# 21_USB.net
KiCad netlist of a schematic drawn in Altium Designer
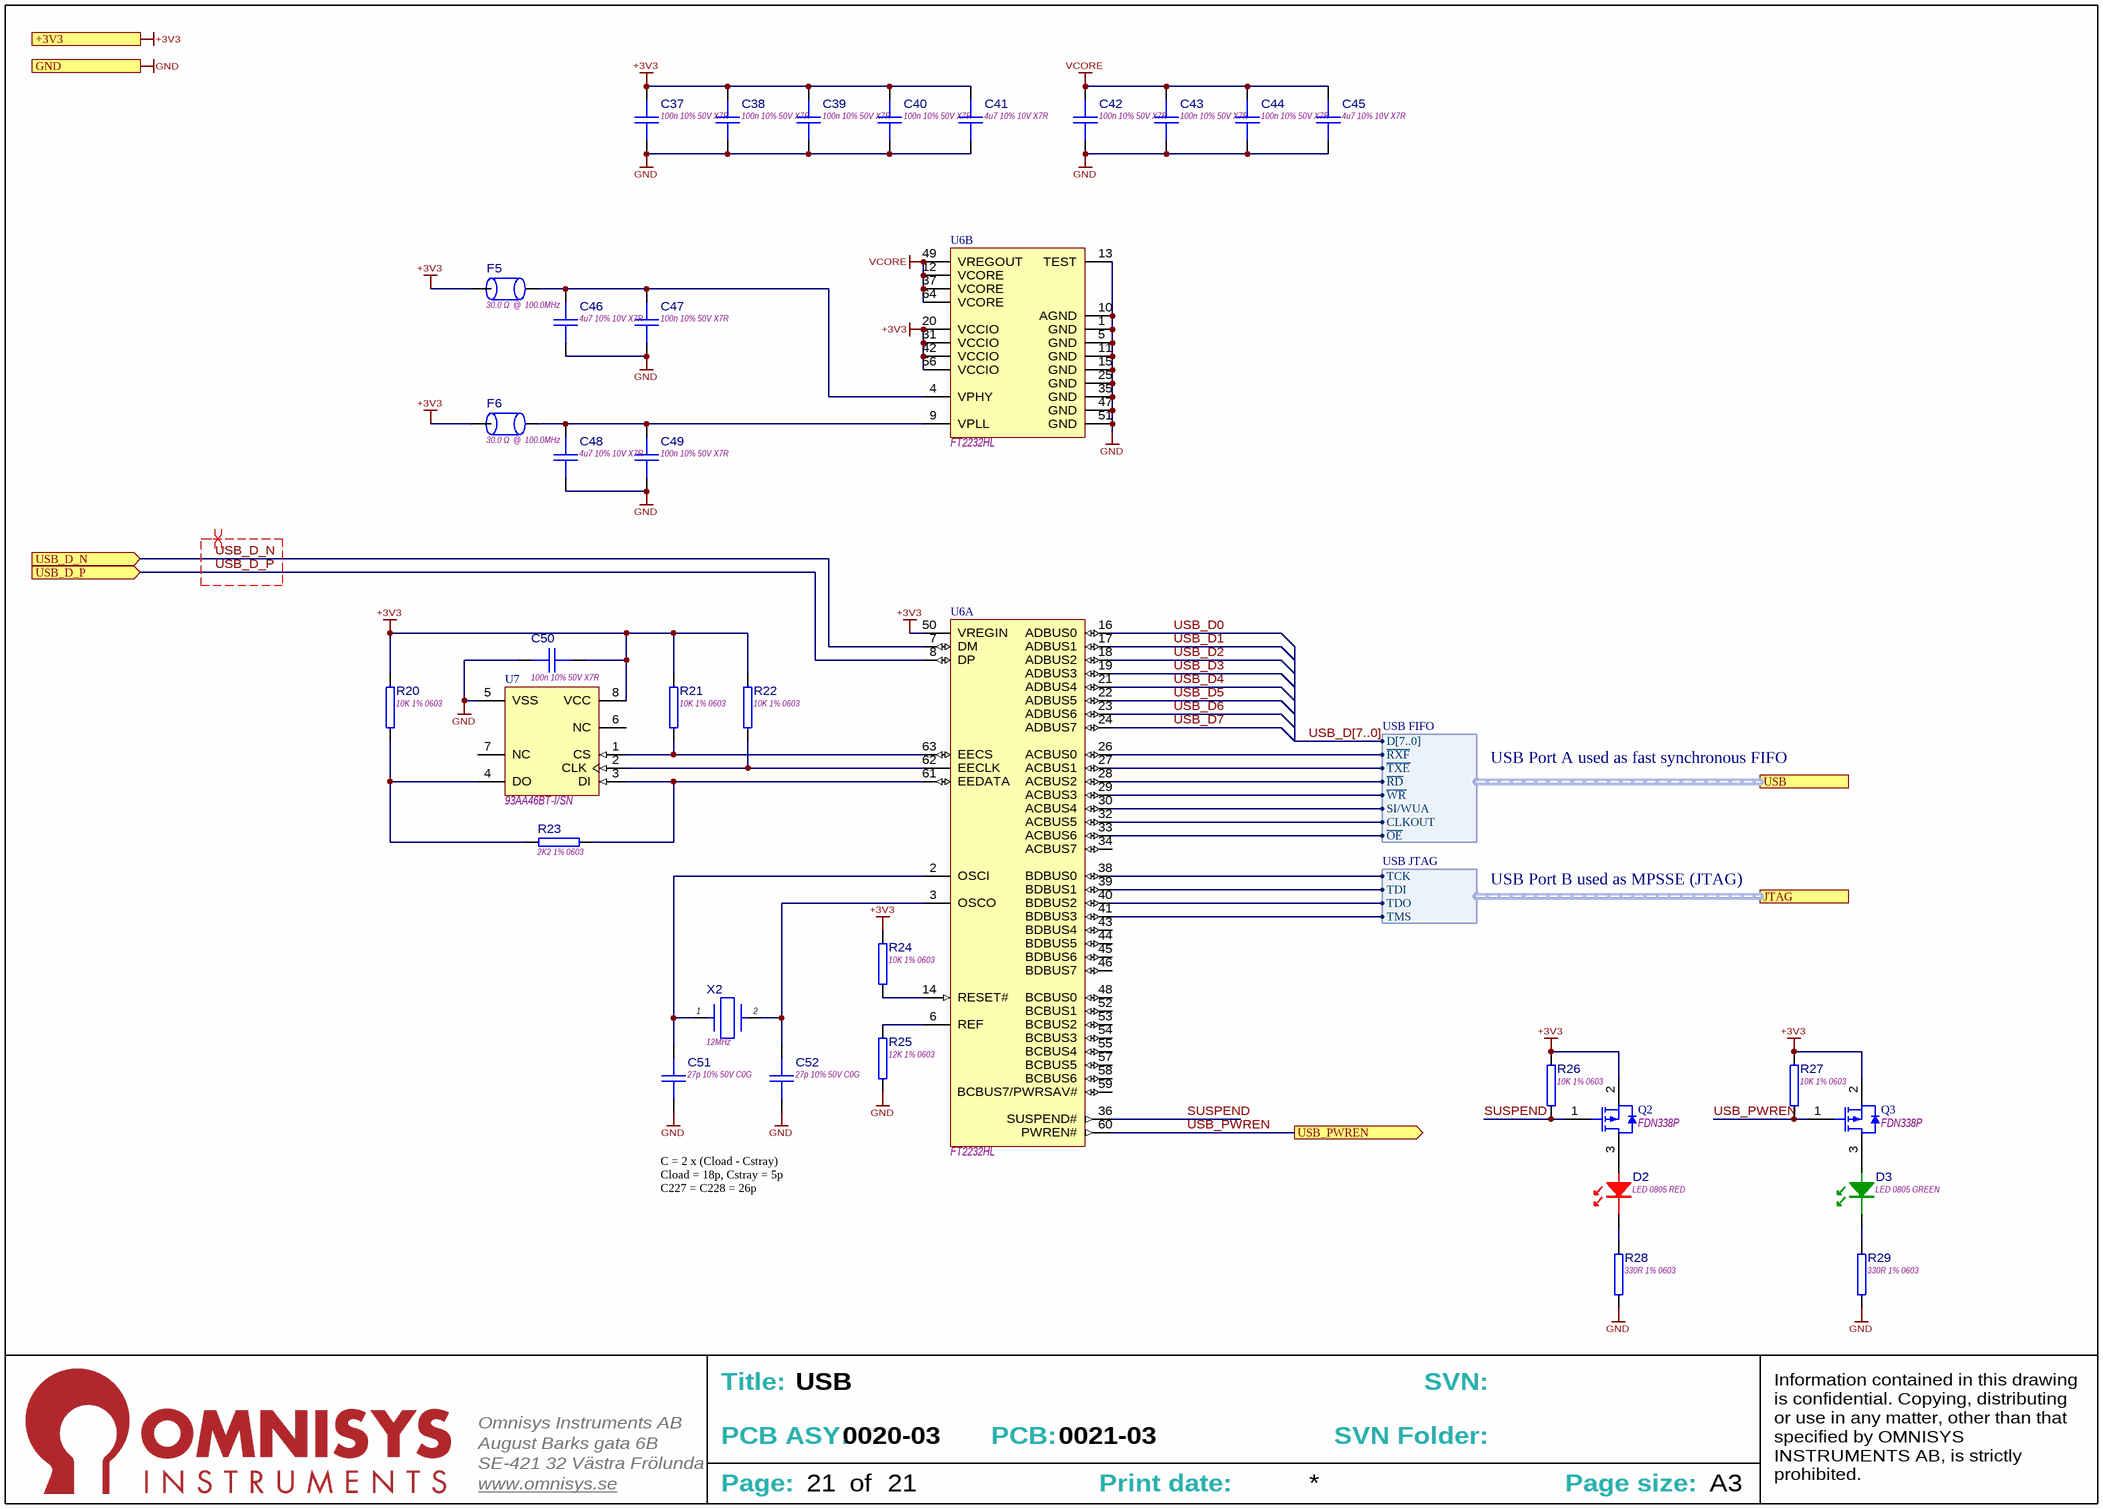
[diagram p0: [21] USB.SchDoc]

(export (version "E")
  (design (tool "Eeschema 10.0.6"))
  (components
    (comp (ref "C37")
      (value "100n 10% 50V X7R")
      (footprint "CAPC1608X90N")
      (description "Ceramic Chip Capacitor, 0603/1608")
      (fields (field (name "TOLERANCE") "10%"))
      (libsource (lib "Omnisys Vault") (part "CAP-2PIN"))
    )
    (comp (ref "C38")
      (value "100n 10% 50V X7R")
      (footprint "CAPC1608X90N")
      (description "Ceramic Chip Capacitor, 0603/1608")
      (fields (field (name "TOLERANCE") "10%"))
      (libsource (lib "Omnisys Vault") (part "CAP-2PIN"))
    )
    (comp (ref "C39")
      (value "100n 10% 50V X7R")
      (footprint "CAPC1608X90N")
      (description "Ceramic Chip Capacitor, 0603/1608")
      (fields (field (name "TOLERANCE") "10%"))
      (libsource (lib "Omnisys Vault") (part "CAP-2PIN"))
    )
    (comp (ref "C40")
      (value "100n 10% 50V X7R")
      (footprint "CAPC1608X90N")
      (description "Ceramic Chip Capacitor, 0603/1608")
      (fields (field (name "TOLERANCE") "10%"))
      (libsource (lib "Omnisys Vault") (part "CAP-2PIN"))
    )
    (comp (ref "C41")
      (value "4u7 10% 10V X7R")
      (footprint "CAPC2012X145N")
      (description "Ceramic Chip Capacitor, 0805/2012")
      (fields (field (name "TOLERANCE") "10%"))
      (libsource (lib "Omnisys Vault") (part "CAP-2PIN"))
    )
    (comp (ref "C42")
      (value "100n 10% 50V X7R")
      (footprint "CAPC1608X90N")
      (description "Ceramic Chip Capacitor, 0603/1608")
      (fields (field (name "TOLERANCE") "10%"))
      (libsource (lib "Omnisys Vault") (part "CAP-2PIN"))
    )
    (comp (ref "C43")
      (value "100n 10% 50V X7R")
      (footprint "CAPC1608X90N")
      (description "Ceramic Chip Capacitor, 0603/1608")
      (fields (field (name "TOLERANCE") "10%"))
      (libsource (lib "Omnisys Vault") (part "CAP-2PIN"))
    )
    (comp (ref "C44")
      (value "100n 10% 50V X7R")
      (footprint "CAPC1608X90N")
      (description "Ceramic Chip Capacitor, 0603/1608")
      (fields (field (name "TOLERANCE") "10%"))
      (libsource (lib "Omnisys Vault") (part "CAP-2PIN"))
    )
    (comp (ref "C45")
      (value "4u7 10% 10V X7R")
      (footprint "CAPC2012X145N")
      (description "Ceramic Chip Capacitor, 0805/2012")
      (fields (field (name "TOLERANCE") "10%"))
      (libsource (lib "Omnisys Vault") (part "CAP-2PIN"))
    )
    (comp (ref "C46")
      (value "4u7 10% 10V X7R")
      (footprint "CAPC2012X145N")
      (description "Ceramic Chip Capacitor, 0805/2012")
      (fields (field (name "TOLERANCE") "10%"))
      (libsource (lib "Omnisys Vault") (part "CAP-2PIN"))
    )
    (comp (ref "C47")
      (value "100n 10% 50V X7R")
      (footprint "CAPC1608X90N")
      (description "Ceramic Chip Capacitor, 0603/1608")
      (fields (field (name "TOLERANCE") "10%"))
      (libsource (lib "Omnisys Vault") (part "CAP-2PIN"))
    )
    (comp (ref "C48")
      (value "4u7 10% 10V X7R")
      (footprint "CAPC2012X145N")
      (description "Ceramic Chip Capacitor, 0805/2012")
      (fields (field (name "TOLERANCE") "10%"))
      (libsource (lib "Omnisys Vault") (part "CAP-2PIN"))
    )
    (comp (ref "C49")
      (value "100n 10% 50V X7R")
      (footprint "CAPC1608X90N")
      (description "Ceramic Chip Capacitor, 0603/1608")
      (fields (field (name "TOLERANCE") "10%"))
      (libsource (lib "Omnisys Vault") (part "CAP-2PIN"))
    )
    (comp (ref "C50")
      (value "100n 10% 50V X7R")
      (footprint "CAPC1608X90N")
      (description "Ceramic Chip Capacitor, 0603/1608")
      (fields (field (name "TOLERANCE") "10%"))
      (libsource (lib "Omnisys Vault") (part "CAP-2PIN"))
    )
    (comp (ref "C51")
      (value "27p 10% 50V C0G")
      (footprint "CAPC1608X90N")
      (description "Ceramic Chip Capacitor, 0603/1608")
      (fields (field (name "TOLERANCE") "5%"))
      (libsource (lib "Omnisys Vault") (part "CAP-2PIN"))
    )
    (comp (ref "C52")
      (value "27p 10% 50V C0G")
      (footprint "CAPC1608X90N")
      (description "Ceramic Chip Capacitor, 0603/1608")
      (fields (field (name "TOLERANCE") "5%"))
      (libsource (lib "Omnisys Vault") (part "CAP-2PIN"))
    )
    (comp (ref "D2")
      (value "LED 0805 RED")
      (footprint "LED2012-RED")
      (libsource (lib "Omnisys Vault") (part "LED-2PIN-RED"))
    )
    (comp (ref "D3")
      (value "LED 0805 GREEN")
      (footprint "LED2012-GREEN")
      (libsource (lib "Omnisys Vault") (part "LED-2PIN-GREEN"))
    )
    (comp (ref "F5")
      (value "30.0 Ω  @  100.0MHz")
      (footprint "INDC2012X11N")
      (description "Ferrite bead, Würth Elektronik WE-CBF 2012 (0805), 74279206 ,  30.0 Ω  @  100.0MHz")
      (fields (field (name "PARTNUMBER") "74279206"))
      (libsource (lib "Omnisys Vault") (part "BEAD-2PIN"))
    )
    (comp (ref "F6")
      (value "30.0 Ω  @  100.0MHz")
      (footprint "INDC2012X11N")
      (description "Ferrite bead, Würth Elektronik WE-CBF 2012 (0805), 74279206 ,  30.0 Ω  @  100.0MHz")
      (fields (field (name "PARTNUMBER") "74279206"))
      (libsource (lib "Omnisys Vault") (part "BEAD-2PIN"))
    )
    (comp (ref "Q2")
      (value "FDN338P")
      (footprint "SOT95P230X110-3N")
      (description "ON SEMICONDUCTOR - FDN338P - P CHANNEL MOSFET, -20V, 1.6A SUPER SOT-3")
      (libsource (lib "Omnisys Vault") (part "PEMOS-GSD-3"))
    )
    (comp (ref "Q3")
      (value "FDN338P")
      (footprint "SOT95P230X110-3N")
      (description "ON SEMICONDUCTOR - FDN338P - P CHANNEL MOSFET, -20V, 1.6A SUPER SOT-3")
      (libsource (lib "Omnisys Vault") (part "PEMOS-GSD-3"))
    )
    (comp (ref "R20")
      (value "10K 1% 0603")
      (footprint "RESC1608N")
      (description "Thick film Chip Resistor, 0603/1608")
      (fields (field (name "POWER") "100mW") (field (name "TOLERANCE") "1%"))
      (libsource (lib "Omnisys Vault") (part "RES-2PIN"))
    )
    (comp (ref "R21")
      (value "10K 1% 0603")
      (footprint "RESC1608N")
      (description "Thick film Chip Resistor, 0603/1608")
      (fields (field (name "POWER") "100mW") (field (name "TOLERANCE") "1%"))
      (libsource (lib "Omnisys Vault") (part "RES-2PIN"))
    )
    (comp (ref "R22")
      (value "10K 1% 0603")
      (footprint "RESC1608N")
      (description "Thick film Chip Resistor, 0603/1608")
      (fields (field (name "POWER") "100mW") (field (name "TOLERANCE") "1%"))
      (libsource (lib "Omnisys Vault") (part "RES-2PIN"))
    )
    (comp (ref "R23")
      (value "2K2 1% 0603")
      (footprint "RESC1608N")
      (description "Thick film Chip Resistor, 0603/1608")
      (fields (field (name "POWER") "100mW") (field (name "TOLERANCE") "1%"))
      (libsource (lib "Omnisys Vault") (part "RES-2PIN"))
    )
    (comp (ref "R24")
      (value "10K 1% 0603")
      (footprint "RESC1608N")
      (description "Thick film Chip Resistor, 0603/1608")
      (fields (field (name "POWER") "100mW") (field (name "TOLERANCE") "1%"))
      (libsource (lib "Omnisys Vault") (part "RES-2PIN"))
    )
    (comp (ref "R25")
      (value "12K 1% 0603")
      (footprint "RESC1608N")
      (description "Thick film Chip Resistor, 0603/1608")
      (fields (field (name "POWER") "100mW") (field (name "TOLERANCE") "1%"))
      (libsource (lib "Omnisys Vault") (part "RES-2PIN"))
    )
    (comp (ref "R26")
      (value "10K 1% 0603")
      (footprint "RESC1608N")
      (description "Thick film Chip Resistor, 0603/1608")
      (fields (field (name "POWER") "100mW") (field (name "TOLERANCE") "1%"))
      (libsource (lib "Omnisys Vault") (part "RES-2PIN"))
    )
    (comp (ref "R27")
      (value "10K 1% 0603")
      (footprint "RESC1608N")
      (description "Thick film Chip Resistor, 0603/1608")
      (fields (field (name "POWER") "100mW") (field (name "TOLERANCE") "1%"))
      (libsource (lib "Omnisys Vault") (part "RES-2PIN"))
    )
    (comp (ref "R28")
      (value "330R 1% 0603")
      (footprint "RESC1608N")
      (description "Thick film Chip Resistor, 0603/1608")
      (fields (field (name "POWER") "100mW") (field (name "TOLERANCE") "1%"))
      (libsource (lib "Omnisys Vault") (part "RES-2PIN"))
    )
    (comp (ref "R29")
      (value "330R 1% 0603")
      (footprint "RESC1608N")
      (description "Thick film Chip Resistor, 0603/1608")
      (fields (field (name "POWER") "100mW") (field (name "TOLERANCE") "1%"))
      (libsource (lib "Omnisys Vault") (part "RES-2PIN"))
    )
    (comp (ref "U6")
      (value "FT2232HL")
      (footprint "FTDI-LQFP-64_L")
      (description "FTDI Chip FT2232HL Dual UART Interface RS232, RS422, RS485 480Mbit/s, 64-Pin, LQFP")
      (libsource (lib "Omnisys Vault") (part "FTDI-FT2232HL-LQFP-64"))
    )
    (comp (ref "U7")
      (value "93AA46BT-I/SN")
      (footprint "SOIC127P600X175-8N")
      (description "IC EEPROM 1KBIT 2MHZ 8SOIC")
      (libsource (lib "Omnisys Vault") (part "MEM-SEEPROM-93AA46B-P-8"))
    )
    (comp (ref "X2")
      (value "12MHz")
      (footprint "XTAL_5x3.2MM")
      (description "12MHz 5 x 3.2 mm SMD GLASS CRYSTAL")
      (libsource (lib "Omnisys Vault") (part "XTAL-2PIN"))
    )
  )
  (nets
    (net (code "6") (name "+3V3") (class "Default")
      (node (ref "C37") (pin "1") (pinfunction "1_1") (pintype "passive"))
      (node (ref "C38") (pin "1") (pinfunction "1_1") (pintype "passive"))
      (node (ref "C39") (pin "1") (pinfunction "1_1") (pintype "passive"))
      (node (ref "C40") (pin "1") (pinfunction "1_1") (pintype "passive"))
      (node (ref "C41") (pin "2") (pinfunction "2_2") (pintype "passive"))
      (node (ref "C50") (pin "2") (pinfunction "2_2") (pintype "passive"))
      (node (ref "F5") (pin "1") (pinfunction "1_1") (pintype "passive"))
      (node (ref "F6") (pin "1") (pinfunction "1_1") (pintype "passive"))
      (node (ref "Q2") (pin "2") (pinfunction "SOURCE_2") (pintype "passive"))
      (node (ref "Q3") (pin "2") (pinfunction "SOURCE_2") (pintype "passive"))
      (node (ref "R20") (pin "2") (pinfunction "2_2") (pintype "passive"))
      (node (ref "R21") (pin "2") (pinfunction "2_2") (pintype "passive"))
      (node (ref "R22") (pin "2") (pinfunction "2_2") (pintype "passive"))
      (node (ref "R24") (pin "1") (pinfunction "1_1") (pintype "passive"))
      (node (ref "R26") (pin "2") (pinfunction "2_2") (pintype "passive"))
      (node (ref "R27") (pin "2") (pinfunction "2_2") (pintype "passive"))
      (node (ref "U6") (pin "20") (pinfunction "VCCIO_20") (pintype "power_in"))
      (node (ref "U6") (pin "31") (pinfunction "VCCIO_31") (pintype "power_in"))
      (node (ref "U6") (pin "42") (pinfunction "VCCIO_42") (pintype "power_in"))
      (node (ref "U6") (pin "50") (pinfunction "VREGIN_50") (pintype "power_in"))
      (node (ref "U6") (pin "56") (pinfunction "VCCIO_56") (pintype "power_in"))
      (node (ref "U7") (pin "8") (pinfunction "VCC_8") (pintype "power_in"))
    )
    (net (code "7") (name "/CLKOUT") (class "Default")
      (node (ref "U6") (pin "32") (pinfunction "ACBUS5_32") (pintype "bidirectional"))
    )
    (net (code "8") (name "/SI{slash}WUA") (class "Default")
      (node (ref "U6") (pin "30") (pinfunction "ACBUS4_30") (pintype "bidirectional"))
    )
    (net (code "9") (name "/SUSPEND") (class "Default")
      (node (ref "Q2") (pin "1") (pinfunction "GATE_1") (pintype "passive"))
      (node (ref "R26") (pin "1") (pinfunction "1_1") (pintype "passive"))
      (node (ref "U6") (pin "36") (pinfunction "SUSPEND#_36") (pintype "output"))
    )
    (net (code "10") (name "/TCK") (class "Default")
      (node (ref "U6") (pin "38") (pinfunction "BDBUS0_38") (pintype "bidirectional"))
    )
    (net (code "11") (name "/TDI") (class "Default")
      (node (ref "U6") (pin "39") (pinfunction "BDBUS1_39") (pintype "bidirectional"))
    )
    (net (code "12") (name "/TDO") (class "Default")
      (node (ref "U6") (pin "40") (pinfunction "BDBUS2_40") (pintype "bidirectional"))
    )
    (net (code "13") (name "/TMS") (class "Default")
      (node (ref "U6") (pin "41") (pinfunction "BDBUS3_41") (pintype "bidirectional"))
    )
    (net (code "14") (name "/USB_D0") (class "Default")
      (node (ref "U6") (pin "16") (pinfunction "ADBUS0_16") (pintype "bidirectional"))
    )
    (net (code "15") (name "/USB_D1") (class "Default")
      (node (ref "U6") (pin "17") (pinfunction "ADBUS1_17") (pintype "bidirectional"))
    )
    (net (code "16") (name "/USB_D2") (class "Default")
      (node (ref "U6") (pin "18") (pinfunction "ADBUS2_18") (pintype "bidirectional"))
    )
    (net (code "17") (name "/USB_D3") (class "Default")
      (node (ref "U6") (pin "19") (pinfunction "ADBUS3_19") (pintype "bidirectional"))
    )
    (net (code "18") (name "/USB_D4") (class "Default")
      (node (ref "U6") (pin "21") (pinfunction "ADBUS4_21") (pintype "bidirectional"))
    )
    (net (code "19") (name "/USB_D5") (class "Default")
      (node (ref "U6") (pin "22") (pinfunction "ADBUS5_22") (pintype "bidirectional"))
    )
    (net (code "20") (name "/USB_D6") (class "Default")
      (node (ref "U6") (pin "23") (pinfunction "ADBUS6_23") (pintype "bidirectional"))
    )
    (net (code "21") (name "/USB_D7") (class "Default")
      (node (ref "U6") (pin "24") (pinfunction "ADBUS7_24") (pintype "bidirectional"))
    )
    (net (code "22") (name "/USB_D_N") (class "Default")
      (node (ref "U6") (pin "7") (pinfunction "DM_7") (pintype "bidirectional"))
    )
    (net (code "23") (name "/USB_D_P") (class "Default")
      (node (ref "U6") (pin "8") (pinfunction "DP_8") (pintype "bidirectional"))
    )
    (net (code "24") (name "/USB_PWREN") (class "Default")
      (node (ref "Q3") (pin "1") (pinfunction "GATE_1") (pintype "passive"))
      (node (ref "R27") (pin "1") (pinfunction "1_1") (pintype "passive"))
      (node (ref "U6") (pin "60") (pinfunction "PWREN#_60") (pintype "output"))
    )
    (net (code "28") (name "/~{OE}") (class "Default")
      (node (ref "U6") (pin "33") (pinfunction "ACBUS6_33") (pintype "bidirectional"))
    )
    (net (code "29") (name "/~{RD}") (class "Default")
      (node (ref "U6") (pin "28") (pinfunction "ACBUS2_28") (pintype "bidirectional"))
    )
    (net (code "30") (name "/~{RXF}") (class "Default")
      (node (ref "U6") (pin "26") (pinfunction "ACBUS0_26") (pintype "bidirectional"))
    )
    (net (code "31") (name "/~{TXE}") (class "Default")
      (node (ref "U6") (pin "27") (pinfunction "ACBUS1_27") (pintype "bidirectional"))
    )
    (net (code "32") (name "/~{WR}") (class "Default")
      (node (ref "U6") (pin "29") (pinfunction "ACBUS3_29") (pintype "bidirectional"))
    )
    (net (code "33") (name "GND") (class "Default")
      (node (ref "C37") (pin "2") (pinfunction "2_2") (pintype "passive"))
      (node (ref "C38") (pin "2") (pinfunction "2_2") (pintype "passive"))
      (node (ref "C39") (pin "2") (pinfunction "2_2") (pintype "passive"))
      (node (ref "C40") (pin "2") (pinfunction "2_2") (pintype "passive"))
      (node (ref "C41") (pin "1") (pinfunction "1_1") (pintype "passive"))
      (node (ref "C42") (pin "2") (pinfunction "2_2") (pintype "passive"))
      (node (ref "C43") (pin "2") (pinfunction "2_2") (pintype "passive"))
      (node (ref "C44") (pin "2") (pinfunction "2_2") (pintype "passive"))
      (node (ref "C45") (pin "1") (pinfunction "1_1") (pintype "passive"))
      (node (ref "C46") (pin "1") (pinfunction "1_1") (pintype "passive"))
      (node (ref "C47") (pin "1") (pinfunction "1_1") (pintype "passive"))
      (node (ref "C48") (pin "1") (pinfunction "1_1") (pintype "passive"))
      (node (ref "C49") (pin "1") (pinfunction "1_1") (pintype "passive"))
      (node (ref "C50") (pin "1") (pinfunction "1_1") (pintype "passive"))
      (node (ref "C51") (pin "1") (pinfunction "1_1") (pintype "passive"))
      (node (ref "C52") (pin "1") (pinfunction "1_1") (pintype "passive"))
      (node (ref "R25") (pin "1") (pinfunction "1_1") (pintype "passive"))
      (node (ref "R28") (pin "1") (pinfunction "1_1") (pintype "passive"))
      (node (ref "R29") (pin "1") (pinfunction "1_1") (pintype "passive"))
      (node (ref "U6") (pin "1") (pinfunction "GND_1") (pintype "power_in"))
      (node (ref "U6") (pin "10") (pinfunction "AGND_10") (pintype "power_in"))
      (node (ref "U6") (pin "11") (pinfunction "GND_11") (pintype "power_in"))
      (node (ref "U6") (pin "13") (pinfunction "TEST_13") (pintype "passive"))
      (node (ref "U6") (pin "15") (pinfunction "GND_15") (pintype "power_in"))
      (node (ref "U6") (pin "25") (pinfunction "GND_25") (pintype "power_in"))
      (node (ref "U6") (pin "35") (pinfunction "GND_35") (pintype "power_in"))
      (node (ref "U6") (pin "47") (pinfunction "GND_47") (pintype "power_in"))
      (node (ref "U6") (pin "5") (pinfunction "GND_5") (pintype "power_in"))
      (node (ref "U6") (pin "51") (pinfunction "GND_51") (pintype "power_in"))
      (node (ref "U7") (pin "5") (pinfunction "VSS_5") (pintype "power_in"))
    )
    (net (code "34") (name "Net-(D2-Pad1)") (class "Default")
      (node (ref "D2") (pin "1") (pintype "passive"))
      (node (ref "R28") (pin "2") (pinfunction "2_2") (pintype "passive"))
    )
    (net (code "35") (name "Net-(D3-Pad1)") (class "Default")
      (node (ref "D3") (pin "1") (pintype "passive"))
      (node (ref "R29") (pin "2") (pinfunction "2_2") (pintype "passive"))
    )
    (net (code "36") (name "Net-(Q2-DRAIN)") (class "Default")
      (node (ref "D2") (pin "2") (pintype "passive"))
      (node (ref "Q2") (pin "3") (pinfunction "DRAIN_3") (pintype "passive"))
    )
    (net (code "37") (name "Net-(Q3-DRAIN)") (class "Default")
      (node (ref "D3") (pin "2") (pintype "passive"))
      (node (ref "Q3") (pin "3") (pinfunction "DRAIN_3") (pintype "passive"))
    )
    (net (code "38") (name "Net-(U6A-EECLK)") (class "Default")
      (node (ref "R22") (pin "1") (pinfunction "1_1") (pintype "passive"))
      (node (ref "U6") (pin "62") (pinfunction "EECLK_62") (pintype "tri_state"))
      (node (ref "U7") (pin "2") (pinfunction "CLK_2") (pintype "input"))
    )
    (net (code "39") (name "Net-(U6A-EECS)") (class "Default")
      (node (ref "R21") (pin "1") (pinfunction "1_1") (pintype "passive"))
      (node (ref "U6") (pin "63") (pinfunction "EECS_63") (pintype "bidirectional"))
      (node (ref "U7") (pin "1") (pinfunction "CS_1") (pintype "input"))
    )
    (net (code "40") (name "Net-(U6A-EEDATA)") (class "Default")
      (node (ref "R23") (pin "2") (pinfunction "2_2") (pintype "passive"))
      (node (ref "U6") (pin "61") (pinfunction "EEDATA_61") (pintype "bidirectional"))
      (node (ref "U7") (pin "3") (pinfunction "DI_3") (pintype "input"))
    )
    (net (code "41") (name "Net-(U6A-OSCI)") (class "Default")
      (node (ref "C51") (pin "2") (pinfunction "2_2") (pintype "passive"))
      (node (ref "U6") (pin "2") (pinfunction "OSCI_2") (pintype "passive"))
      (node (ref "X2") (pin "1") (pinfunction "1_1") (pintype "passive"))
    )
    (net (code "42") (name "Net-(U6A-OSCO)") (class "Default")
      (node (ref "C52") (pin "2") (pinfunction "2_2") (pintype "passive"))
      (node (ref "U6") (pin "3") (pinfunction "OSCO_3") (pintype "passive"))
      (node (ref "X2") (pin "2") (pinfunction "2_2") (pintype "passive"))
    )
    (net (code "43") (name "Net-(U6A-REF)") (class "Default")
      (node (ref "R25") (pin "2") (pinfunction "2_2") (pintype "passive"))
      (node (ref "U6") (pin "6") (pinfunction "REF_6") (pintype "passive"))
    )
    (net (code "44") (name "Net-(U6A-RESET#)") (class "Default")
      (node (ref "R24") (pin "2") (pinfunction "2_2") (pintype "passive"))
      (node (ref "U6") (pin "14") (pinfunction "RESET#_14") (pintype "input"))
    )
    (net (code "45") (name "Net-(U6B-VPHY)") (class "Default")
      (node (ref "C46") (pin "2") (pinfunction "2_2") (pintype "passive"))
      (node (ref "C47") (pin "2") (pinfunction "2_2") (pintype "passive"))
      (node (ref "F5") (pin "2") (pinfunction "2_2") (pintype "passive"))
      (node (ref "U6") (pin "4") (pinfunction "VPHY_4") (pintype "power_in"))
    )
    (net (code "46") (name "Net-(U6B-VPLL)") (class "Default")
      (node (ref "C48") (pin "2") (pinfunction "2_2") (pintype "passive"))
      (node (ref "C49") (pin "2") (pinfunction "2_2") (pintype "passive"))
      (node (ref "F6") (pin "2") (pinfunction "2_2") (pintype "passive"))
      (node (ref "U6") (pin "9") (pinfunction "VPLL_9") (pintype "power_in"))
    )
    (net (code "47") (name "Net-(U7-DO)") (class "Default")
      (node (ref "R20") (pin "1") (pinfunction "1_1") (pintype "passive"))
      (node (ref "R23") (pin "1") (pinfunction "1_1") (pintype "passive"))
      (node (ref "U7") (pin "4") (pinfunction "DO_4") (pintype "tri_state"))
    )
    (net (code "48") (name "VCORE") (class "Default")
      (node (ref "C42") (pin "1") (pinfunction "1_1") (pintype "passive"))
      (node (ref "C43") (pin "1") (pinfunction "1_1") (pintype "passive"))
      (node (ref "C44") (pin "1") (pinfunction "1_1") (pintype "passive"))
      (node (ref "C45") (pin "2") (pinfunction "2_2") (pintype "passive"))
      (node (ref "U6") (pin "12") (pinfunction "VCORE_12") (pintype "power_in"))
      (node (ref "U6") (pin "37") (pinfunction "VCORE_37") (pintype "power_in"))
      (node (ref "U6") (pin "49") (pinfunction "VREGOUT_49") (pintype "power_in"))
      (node (ref "U6") (pin "64") (pinfunction "VCORE_64") (pintype "power_in"))
    )
    (net (code "49") (name "unconnected-(U6A-ACBUS7-Pad34)") (class "Default")
      (node (ref "U6") (pin "34") (pinfunction "ACBUS7_34") (pintype "bidirectional"))
    )
    (net (code "50") (name "unconnected-(U6A-BCBUS0-Pad48)") (class "Default")
      (node (ref "U6") (pin "48") (pinfunction "BCBUS0_48") (pintype "bidirectional"))
    )
    (net (code "51") (name "unconnected-(U6A-BCBUS1-Pad52)") (class "Default")
      (node (ref "U6") (pin "52") (pinfunction "BCBUS1_52") (pintype "bidirectional"))
    )
    (net (code "52") (name "unconnected-(U6A-BCBUS2-Pad53)") (class "Default")
      (node (ref "U6") (pin "53") (pinfunction "BCBUS2_53") (pintype "bidirectional"))
    )
    (net (code "53") (name "unconnected-(U6A-BCBUS3-Pad54)") (class "Default")
      (node (ref "U6") (pin "54") (pinfunction "BCBUS3_54") (pintype "bidirectional"))
    )
    (net (code "54") (name "unconnected-(U6A-BCBUS4-Pad55)") (class "Default")
      (node (ref "U6") (pin "55") (pinfunction "BCBUS4_55") (pintype "bidirectional"))
    )
    (net (code "55") (name "unconnected-(U6A-BCBUS5-Pad57)") (class "Default")
      (node (ref "U6") (pin "57") (pinfunction "BCBUS5_57") (pintype "bidirectional"))
    )
    (net (code "56") (name "unconnected-(U6A-BCBUS6-Pad58)") (class "Default")
      (node (ref "U6") (pin "58") (pinfunction "BCBUS6_58") (pintype "bidirectional"))
    )
    (net (code "57") (name "unconnected-(U6A-BCBUS7{slash}PWRSAV#-Pad59)") (class "Default")
      (node (ref "U6") (pin "59") (pinfunction "BCBUS7/PWRSAV#_59") (pintype "bidirectional"))
    )
    (net (code "58") (name "unconnected-(U6A-BDBUS4-Pad43)") (class "Default")
      (node (ref "U6") (pin "43") (pinfunction "BDBUS4_43") (pintype "bidirectional"))
    )
    (net (code "59") (name "unconnected-(U6A-BDBUS5-Pad44)") (class "Default")
      (node (ref "U6") (pin "44") (pinfunction "BDBUS5_44") (pintype "bidirectional"))
    )
    (net (code "60") (name "unconnected-(U6A-BDBUS6-Pad45)") (class "Default")
      (node (ref "U6") (pin "45") (pinfunction "BDBUS6_45") (pintype "bidirectional"))
    )
    (net (code "61") (name "unconnected-(U6A-BDBUS7-Pad46)") (class "Default")
      (node (ref "U6") (pin "46") (pinfunction "BDBUS7_46") (pintype "bidirectional"))
    )
    (net (code "62") (name "unconnected-(U7-NC-Pad6)") (class "Default")
      (node (ref "U7") (pin "6") (pinfunction "NC_6") (pintype "passive"))
    )
    (net (code "63") (name "unconnected-(U7-NC-Pad7)") (class "Default")
      (node (ref "U7") (pin "7") (pinfunction "NC_7") (pintype "passive"))
    )
  )
)
